# gamepad.net
KiCad netlist of a schematic drawn in EAGLE
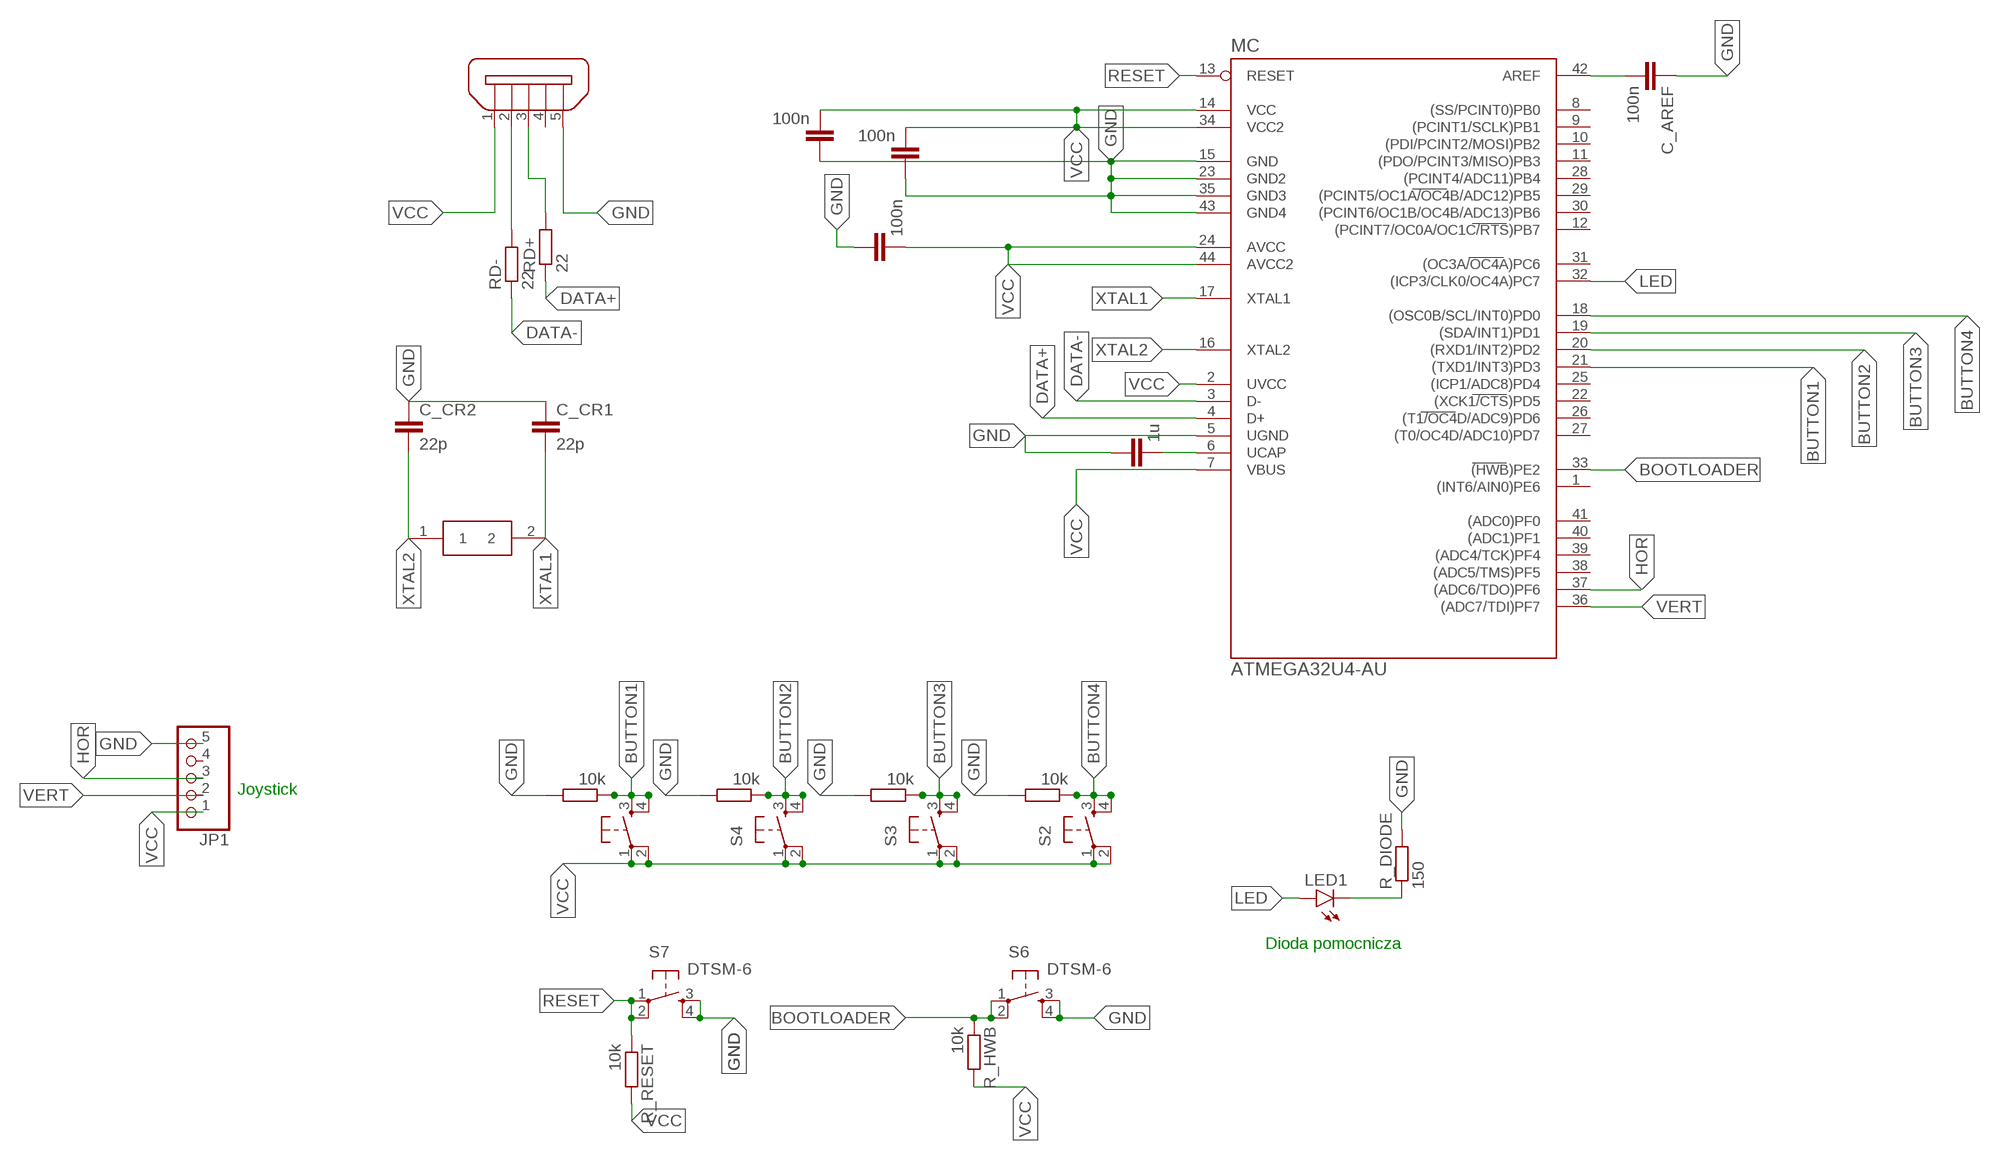
[diagram p0: schematic, sheet 1]

(export (version "E")
  (design (tool "Eeschema 10.0.6"))
  (components
    (comp (ref "C_AREF")
      (value "100n")
      (footprint "eagle-import:C0805")
      (libsource (lib "eagle-import") (part "C-EUC0805"))
    )
    (comp (ref "C_CR1")
      (value "22p")
      (footprint "eagle-import:C0805")
      (libsource (lib "eagle-import") (part "C-EUC0805"))
    )
    (comp (ref "C_CR2")
      (value "22p")
      (footprint "eagle-import:C0805")
      (libsource (lib "eagle-import") (part "C-EUC0805"))
    )
    (comp (ref "C_LPF")
      (value "100n")
      (footprint "eagle-import:C0805")
      (libsource (lib "eagle-import") (part "C-EUC0805"))
    )
    (comp (ref "C_UCAPR")
      (value "1u")
      (footprint "eagle-import:C0805")
      (libsource (lib "eagle-import") (part "C-EUC0805"))
    )
    (comp (ref "C_VCC_TO_GND_14")
      (value "100n")
      (footprint "eagle-import:C0805")
      (libsource (lib "eagle-import") (part "C-EUC0805"))
    )
    (comp (ref "C_VCC_TO_GND_33")
      (value "100n")
      (footprint "eagle-import:C0805")
      (libsource (lib "eagle-import") (part "C-EUC0805"))
    )
    (comp (ref "JP1")
      (value "PINHD-1X5")
      (footprint "eagle-import:1X05")
      (libsource (lib "eagle-import") (part "PINHD-1X5"))
    )
    (comp (ref "LED1")
      (value "LEDSML1206")
      (footprint "eagle-import:SML1206")
      (libsource (lib "eagle-import") (part "LEDSML1206"))
    )
    (comp (ref "MC")
      (value "ATMEGA32U4-AU")
      (footprint "eagle-import:TQFP44")
      (libsource (lib "eagle-import") (part "ATMEGA32U4-AU"))
    )
    (comp (ref "QUARTZ_OSC_ZAST")
      (value "ECS-160-8-30Q-VY-TR")
      (footprint "eagle-import:ECS80830QVSTR")
      (fields (field (name "MOUSER_PART_NUMBER") "520-160-8-30Q-VYT"))
      (libsource (lib "eagle-import") (part "ECS-160-8-30Q-VY-TR"))
    )
    (comp (ref "RD+")
      (value "22")
      (footprint "eagle-import:R0805")
      (libsource (lib "eagle-import") (part "R-EU_R0805"))
    )
    (comp (ref "RD-")
      (value "22")
      (footprint "eagle-import:R0805")
      (libsource (lib "eagle-import") (part "R-EU_R0805"))
    )
    (comp (ref "R_DIODE")
      (value "150")
      (footprint "eagle-import:R2512")
      (libsource (lib "eagle-import") (part "R-EU_R2512"))
    )
    (comp (ref "R_HWB")
      (value "10k")
      (footprint "eagle-import:R0805")
      (libsource (lib "eagle-import") (part "R-EU_R0805"))
    )
    (comp (ref "R_H_SWITCH1")
      (value "10k")
      (footprint "eagle-import:R0805")
      (libsource (lib "eagle-import") (part "R-EU_R0805"))
    )
    (comp (ref "R_H_SWITCH2")
      (value "10k")
      (footprint "eagle-import:R0805")
      (libsource (lib "eagle-import") (part "R-EU_R0805"))
    )
    (comp (ref "R_H_SWITCH3")
      (value "10k")
      (footprint "eagle-import:R0805")
      (libsource (lib "eagle-import") (part "R-EU_R0805"))
    )
    (comp (ref "R_H_SWITCH4")
      (value "10k")
      (footprint "eagle-import:R0805")
      (libsource (lib "eagle-import") (part "R-EU_R0805"))
    )
    (comp (ref "R_RESET")
      (value "10k")
      (footprint "eagle-import:R0805")
      (libsource (lib "eagle-import") (part "R-EU_R0805"))
    )
    (comp (ref "S2")
      (value "DTSM-6")
      (footprint "eagle-import:DTSM-6")
      (libsource (lib "eagle-import") (part "DTSM-6"))
    )
    (comp (ref "S3")
      (value "DTSM-6")
      (footprint "eagle-import:DTSM-6")
      (libsource (lib "eagle-import") (part "DTSM-6"))
    )
    (comp (ref "S4")
      (value "DTSM-6")
      (footprint "eagle-import:DTSM-6")
      (libsource (lib "eagle-import") (part "DTSM-6"))
    )
    (comp (ref "S5")
      (value "DTSM-6")
      (footprint "eagle-import:DTSM-6")
      (libsource (lib "eagle-import") (part "DTSM-6"))
    )
    (comp (ref "S6")
      (value "DTSM-6")
      (footprint "eagle-import:DTSM-6")
      (libsource (lib "eagle-import") (part "DTSM-6"))
    )
    (comp (ref "S7")
      (value "DTSM-6")
      (footprint "eagle-import:DTSM-6")
      (libsource (lib "eagle-import") (part "DTSM-6"))
    )
    (comp (ref "X1")
      (value "ZX62D-B-5PA8")
      (footprint "eagle-import:ZX62D-B-5PA8")
      (fields (field (name "MF") "Hirose"))
      (libsource (lib "eagle-import") (part "ZX62D-B-5PA8"))
    )
  )
  (nets
    (net (code "1") (name "BOOTLOADER") (class "Default")
      (node (ref "MC") (pin "33") (pinfunction "(HWB)PE2_33") (pintype "bidirectional"))
      (node (ref "R_HWB") (pin "1") (pinfunction "1_1") (pintype "passive"))
      (node (ref "S6") (pin "1") (pinfunction "1_1") (pintype "passive"))
      (node (ref "S6") (pin "2") (pinfunction "2_2") (pintype "passive"))
    )
    (net (code "2") (name "BUTTON1") (class "Default")
      (node (ref "MC") (pin "21") (pinfunction "(TXD1/INT3)PD3_21") (pintype "bidirectional"))
      (node (ref "R_H_SWITCH1") (pin "1") (pinfunction "1_1") (pintype "passive"))
      (node (ref "S5") (pin "3") (pinfunction "3_3") (pintype "passive"))
      (node (ref "S5") (pin "4") (pinfunction "4_4") (pintype "passive"))
    )
    (net (code "3") (name "BUTTON2") (class "Default")
      (node (ref "MC") (pin "20") (pinfunction "(RXD1/INT2)PD2_20") (pintype "bidirectional"))
      (node (ref "R_H_SWITCH2") (pin "1") (pinfunction "1_1") (pintype "passive"))
      (node (ref "S4") (pin "3") (pinfunction "3_3") (pintype "passive"))
      (node (ref "S4") (pin "4") (pinfunction "4_4") (pintype "passive"))
    )
    (net (code "4") (name "BUTTON3") (class "Default")
      (node (ref "MC") (pin "19") (pinfunction "(SDA/INT1)PD1_19") (pintype "bidirectional"))
      (node (ref "R_H_SWITCH3") (pin "1") (pinfunction "1_1") (pintype "passive"))
      (node (ref "S3") (pin "3") (pinfunction "3_3") (pintype "passive"))
      (node (ref "S3") (pin "4") (pinfunction "4_4") (pintype "passive"))
    )
    (net (code "5") (name "BUTTON4") (class "Default")
      (node (ref "MC") (pin "18") (pinfunction "(OSC0B/SCL/INT0)PD0_18") (pintype "bidirectional"))
      (node (ref "R_H_SWITCH4") (pin "1") (pinfunction "1_1") (pintype "passive"))
      (node (ref "S2") (pin "3") (pinfunction "3_3") (pintype "passive"))
      (node (ref "S2") (pin "4") (pinfunction "4_4") (pintype "passive"))
    )
    (net (code "6") (name "DATA+") (class "Default")
      (node (ref "MC") (pin "4") (pinfunction "D+_4") (pintype "bidirectional"))
      (node (ref "RD+") (pin "1") (pinfunction "1_1") (pintype "passive"))
    )
    (net (code "7") (name "DATA-") (class "Default")
      (node (ref "MC") (pin "3") (pinfunction "D-_3") (pintype "bidirectional"))
      (node (ref "RD-") (pin "1") (pinfunction "1_1") (pintype "passive"))
    )
    (net (code "8") (name "GND") (class "Default")
      (node (ref "C_AREF") (pin "1") (pinfunction "1_1") (pintype "passive"))
      (node (ref "C_CR1") (pin "1") (pinfunction "1_1") (pintype "passive"))
      (node (ref "C_CR2") (pin "1") (pinfunction "1_1") (pintype "passive"))
      (node (ref "C_LPF") (pin "1") (pinfunction "1_1") (pintype "passive"))
      (node (ref "C_UCAPR") (pin "1") (pinfunction "1_1") (pintype "passive"))
      (node (ref "C_VCC_TO_GND_14") (pin "1") (pinfunction "1_1") (pintype "passive"))
      (node (ref "C_VCC_TO_GND_33") (pin "1") (pinfunction "1_1") (pintype "passive"))
      (node (ref "JP1") (pin "5") (pinfunction "5_5") (pintype "passive"))
      (node (ref "MC") (pin "15") (pinfunction "GND_15") (pintype "bidirectional"))
      (node (ref "MC") (pin "23") (pinfunction "GND2_23") (pintype "bidirectional"))
      (node (ref "MC") (pin "35") (pinfunction "GND3_35") (pintype "bidirectional"))
      (node (ref "MC") (pin "43") (pinfunction "GND4_43") (pintype "bidirectional"))
      (node (ref "MC") (pin "5") (pinfunction "UGND_5") (pintype "bidirectional"))
      (node (ref "R_DIODE") (pin "2") (pinfunction "2_2") (pintype "passive"))
      (node (ref "R_H_SWITCH1") (pin "2") (pinfunction "2_2") (pintype "passive"))
      (node (ref "R_H_SWITCH2") (pin "2") (pinfunction "2_2") (pintype "passive"))
      (node (ref "R_H_SWITCH3") (pin "2") (pinfunction "2_2") (pintype "passive"))
      (node (ref "R_H_SWITCH4") (pin "2") (pinfunction "2_2") (pintype "passive"))
      (node (ref "S6") (pin "3") (pinfunction "3_3") (pintype "passive"))
      (node (ref "S6") (pin "4") (pinfunction "4_4") (pintype "passive"))
      (node (ref "S7") (pin "3") (pinfunction "3_3") (pintype "passive"))
      (node (ref "S7") (pin "4") (pinfunction "4_4") (pintype "passive"))
      (node (ref "X1") (pin "5") (pinfunction "5_5") (pintype "passive"))
    )
    (net (code "9") (name "HOR") (class "Default")
      (node (ref "JP1") (pin "3") (pinfunction "3_3") (pintype "passive"))
      (node (ref "MC") (pin "37") (pinfunction "(ADC6/TDO)PF6_37") (pintype "bidirectional"))
    )
    (net (code "10") (name "LED") (class "Default")
      (node (ref "LED1") (pin "A") (pinfunction "A_A") (pintype "passive"))
      (node (ref "MC") (pin "32") (pinfunction "(ICP3/CLK0/OC4A)PC7_32") (pintype "bidirectional"))
    )
    (net (code "11") (name "Net-(LED1-PadC)") (class "Default")
      (node (ref "LED1") (pin "C") (pinfunction "C_C") (pintype "passive"))
      (node (ref "R_DIODE") (pin "1") (pinfunction "1_1") (pintype "passive"))
    )
    (net (code "12") (name "Net-(MC-AREF)") (class "Default")
      (node (ref "C_AREF") (pin "2") (pinfunction "2_2") (pintype "passive"))
      (node (ref "MC") (pin "42") (pinfunction "AREF_42") (pintype "bidirectional"))
    )
    (net (code "13") (name "Net-(MC-UCAP)") (class "Default")
      (node (ref "C_UCAPR") (pin "2") (pinfunction "2_2") (pintype "passive"))
      (node (ref "MC") (pin "6") (pinfunction "UCAP_6") (pintype "bidirectional"))
    )
    (net (code "14") (name "Net-(RD+-Pad2)") (class "Default")
      (node (ref "RD+") (pin "2") (pinfunction "2_2") (pintype "passive"))
      (node (ref "X1") (pin "3") (pinfunction "3_3") (pintype "passive"))
    )
    (net (code "15") (name "Net-(RD--Pad2)") (class "Default")
      (node (ref "RD-") (pin "2") (pinfunction "2_2") (pintype "passive"))
      (node (ref "X1") (pin "2") (pinfunction "2_2") (pintype "passive"))
    )
    (net (code "16") (name "RESET") (class "Default")
      (node (ref "MC") (pin "13") (pinfunction "RESET_13") (pintype "bidirectional"))
      (node (ref "R_RESET") (pin "1") (pinfunction "1_1") (pintype "passive"))
      (node (ref "S7") (pin "1") (pinfunction "1_1") (pintype "passive"))
      (node (ref "S7") (pin "2") (pinfunction "2_2") (pintype "passive"))
    )
    (net (code "17") (name "VCC") (class "Default")
      (node (ref "C_LPF") (pin "2") (pinfunction "2_2") (pintype "passive"))
      (node (ref "C_VCC_TO_GND_14") (pin "2") (pinfunction "2_2") (pintype "passive"))
      (node (ref "C_VCC_TO_GND_33") (pin "2") (pinfunction "2_2") (pintype "passive"))
      (node (ref "JP1") (pin "1") (pinfunction "1_1") (pintype "passive"))
      (node (ref "MC") (pin "14") (pinfunction "VCC_14") (pintype "bidirectional"))
      (node (ref "MC") (pin "2") (pinfunction "UVCC_2") (pintype "bidirectional"))
      (node (ref "MC") (pin "24") (pinfunction "AVCC_24") (pintype "bidirectional"))
      (node (ref "MC") (pin "34") (pinfunction "VCC2_34") (pintype "bidirectional"))
      (node (ref "MC") (pin "44") (pinfunction "AVCC2_44") (pintype "bidirectional"))
      (node (ref "MC") (pin "7") (pinfunction "VBUS_7") (pintype "bidirectional"))
      (node (ref "R_HWB") (pin "2") (pinfunction "2_2") (pintype "passive"))
      (node (ref "R_RESET") (pin "2") (pinfunction "2_2") (pintype "passive"))
      (node (ref "S2") (pin "1") (pinfunction "1_1") (pintype "passive"))
      (node (ref "S2") (pin "2") (pinfunction "2_2") (pintype "passive"))
      (node (ref "S3") (pin "1") (pinfunction "1_1") (pintype "passive"))
      (node (ref "S3") (pin "2") (pinfunction "2_2") (pintype "passive"))
      (node (ref "S4") (pin "1") (pinfunction "1_1") (pintype "passive"))
      (node (ref "S4") (pin "2") (pinfunction "2_2") (pintype "passive"))
      (node (ref "S5") (pin "1") (pinfunction "1_1") (pintype "passive"))
      (node (ref "S5") (pin "2") (pinfunction "2_2") (pintype "passive"))
      (node (ref "X1") (pin "1") (pinfunction "1_1") (pintype "passive"))
    )
    (net (code "18") (name "VERT") (class "Default")
      (node (ref "JP1") (pin "2") (pinfunction "2_2") (pintype "passive"))
      (node (ref "MC") (pin "36") (pinfunction "(ADC7/TDI)PF7_36") (pintype "bidirectional"))
    )
    (net (code "19") (name "XTAL1") (class "Default")
      (node (ref "C_CR1") (pin "2") (pinfunction "2_2") (pintype "passive"))
      (node (ref "MC") (pin "17") (pinfunction "XTAL1_17") (pintype "bidirectional"))
      (node (ref "QUARTZ_OSC_ZAST") (pin "2") (pinfunction "2_2") (pintype "bidirectional"))
    )
    (net (code "20") (name "XTAL2") (class "Default")
      (node (ref "C_CR2") (pin "2") (pinfunction "2_2") (pintype "passive"))
      (node (ref "MC") (pin "16") (pinfunction "XTAL2_16") (pintype "bidirectional"))
      (node (ref "QUARTZ_OSC_ZAST") (pin "1") (pinfunction "1_1") (pintype "bidirectional"))
    )
    (net (code "21") (name "unconnected-(JP1-Pad4)") (class "Default")
      (node (ref "JP1") (pin "4") (pinfunction "4_4") (pintype "passive"))
    )
    (net (code "22") (name "unconnected-(MC-(ADC0)PF0-Pad41)") (class "Default")
      (node (ref "MC") (pin "41") (pinfunction "(ADC0)PF0_41") (pintype "bidirectional"))
    )
    (net (code "23") (name "unconnected-(MC-(ADC1)PF1-Pad40)") (class "Default")
      (node (ref "MC") (pin "40") (pinfunction "(ADC1)PF1_40") (pintype "bidirectional"))
    )
    (net (code "24") (name "unconnected-(MC-(ADC4{slash}TCK)PF4-Pad39)") (class "Default")
      (node (ref "MC") (pin "39") (pinfunction "(ADC4/TCK)PF4_39") (pintype "bidirectional"))
    )
    (net (code "25") (name "unconnected-(MC-(ADC5{slash}TMS)PF5-Pad38)") (class "Default")
      (node (ref "MC") (pin "38") (pinfunction "(ADC5/TMS)PF5_38") (pintype "bidirectional"))
    )
    (net (code "26") (name "unconnected-(MC-(ICP1{slash}ADC8)PD4-Pad25)") (class "Default")
      (node (ref "MC") (pin "25") (pinfunction "(ICP1/ADC8)PD4_25") (pintype "bidirectional"))
    )
    (net (code "27") (name "unconnected-(MC-(INT6{slash}AIN0)PE6-Pad1)") (class "Default")
      (node (ref "MC") (pin "1") (pinfunction "(INT6/AIN0)PE6_1") (pintype "bidirectional"))
    )
    (net (code "28") (name "unconnected-(MC-(OC3A{slash}OC4A)PC6-Pad31)") (class "Default")
      (node (ref "MC") (pin "31") (pinfunction "(OC3A/OC4A)PC6_31") (pintype "bidirectional"))
    )
    (net (code "29") (name "unconnected-(MC-(PCINT1{slash}SCLK)PB1-Pad9)") (class "Default")
      (node (ref "MC") (pin "9") (pinfunction "(PCINT1/SCLK)PB1_9") (pintype "bidirectional"))
    )
    (net (code "30") (name "unconnected-(MC-(PCINT4{slash}ADC11)PB4-Pad28)") (class "Default")
      (node (ref "MC") (pin "28") (pinfunction "(PCINT4/ADC11)PB4_28") (pintype "bidirectional"))
    )
    (net (code "31") (name "unconnected-(MC-(PCINT5{slash}OC1A{slash}OC4B{slash}ADC12)PB5-Pad29)") (class "Default")
      (node (ref "MC") (pin "29") (pinfunction "(PCINT5/OC1A/OC4B/ADC12)PB5_29") (pintype "bidirectional"))
    )
    (net (code "32") (name "unconnected-(MC-(PCINT6{slash}OC1B{slash}OC4B{slash}ADC13)PB6-Pad30)") (class "Default")
      (node (ref "MC") (pin "30") (pinfunction "(PCINT6/OC1B/OC4B/ADC13)PB6_30") (pintype "bidirectional"))
    )
    (net (code "33") (name "unconnected-(MC-(PCINT7{slash}OC0A{slash}OC1C{slash}RTS)PB7-Pad12)") (class "Default")
      (node (ref "MC") (pin "12") (pinfunction "(PCINT7/OC0A/OC1C/RTS)PB7_12") (pintype "bidirectional"))
    )
    (net (code "34") (name "unconnected-(MC-(PDI{slash}PCINT2{slash}MOSI)PB2-Pad10)") (class "Default")
      (node (ref "MC") (pin "10") (pinfunction "(PDI/PCINT2/MOSI)PB2_10") (pintype "bidirectional"))
    )
    (net (code "35") (name "unconnected-(MC-(PDO{slash}PCINT3{slash}MISO)PB3-Pad11)") (class "Default")
      (node (ref "MC") (pin "11") (pinfunction "(PDO/PCINT3/MISO)PB3_11") (pintype "bidirectional"))
    )
    (net (code "36") (name "unconnected-(MC-(SS{slash}PCINT0)PB0-Pad8)") (class "Default")
      (node (ref "MC") (pin "8") (pinfunction "(SS/PCINT0)PB0_8") (pintype "bidirectional"))
    )
    (net (code "37") (name "unconnected-(MC-(T0{slash}OC4D{slash}ADC10)PD7-Pad27)") (class "Default")
      (node (ref "MC") (pin "27") (pinfunction "(T0/OC4D/ADC10)PD7_27") (pintype "bidirectional"))
    )
    (net (code "38") (name "unconnected-(MC-(T1{slash}OC4D{slash}ADC9)PD6-Pad26)") (class "Default")
      (node (ref "MC") (pin "26") (pinfunction "(T1/OC4D/ADC9)PD6_26") (pintype "bidirectional"))
    )
    (net (code "39") (name "unconnected-(MC-(XCK1{slash}CTS)PD5-Pad22)") (class "Default")
      (node (ref "MC") (pin "22") (pinfunction "(XCK1/CTS)PD5_22") (pintype "bidirectional"))
    )
    (net (code "40") (name "unconnected-(X1-Pad4)") (class "Default")
      (node (ref "X1") (pin "4") (pinfunction "4_4") (pintype "passive"))
    )
  )
)
